# Dual_Holding_Dongle.net
KiCad netlist of a schematic drawn in Altium Designer
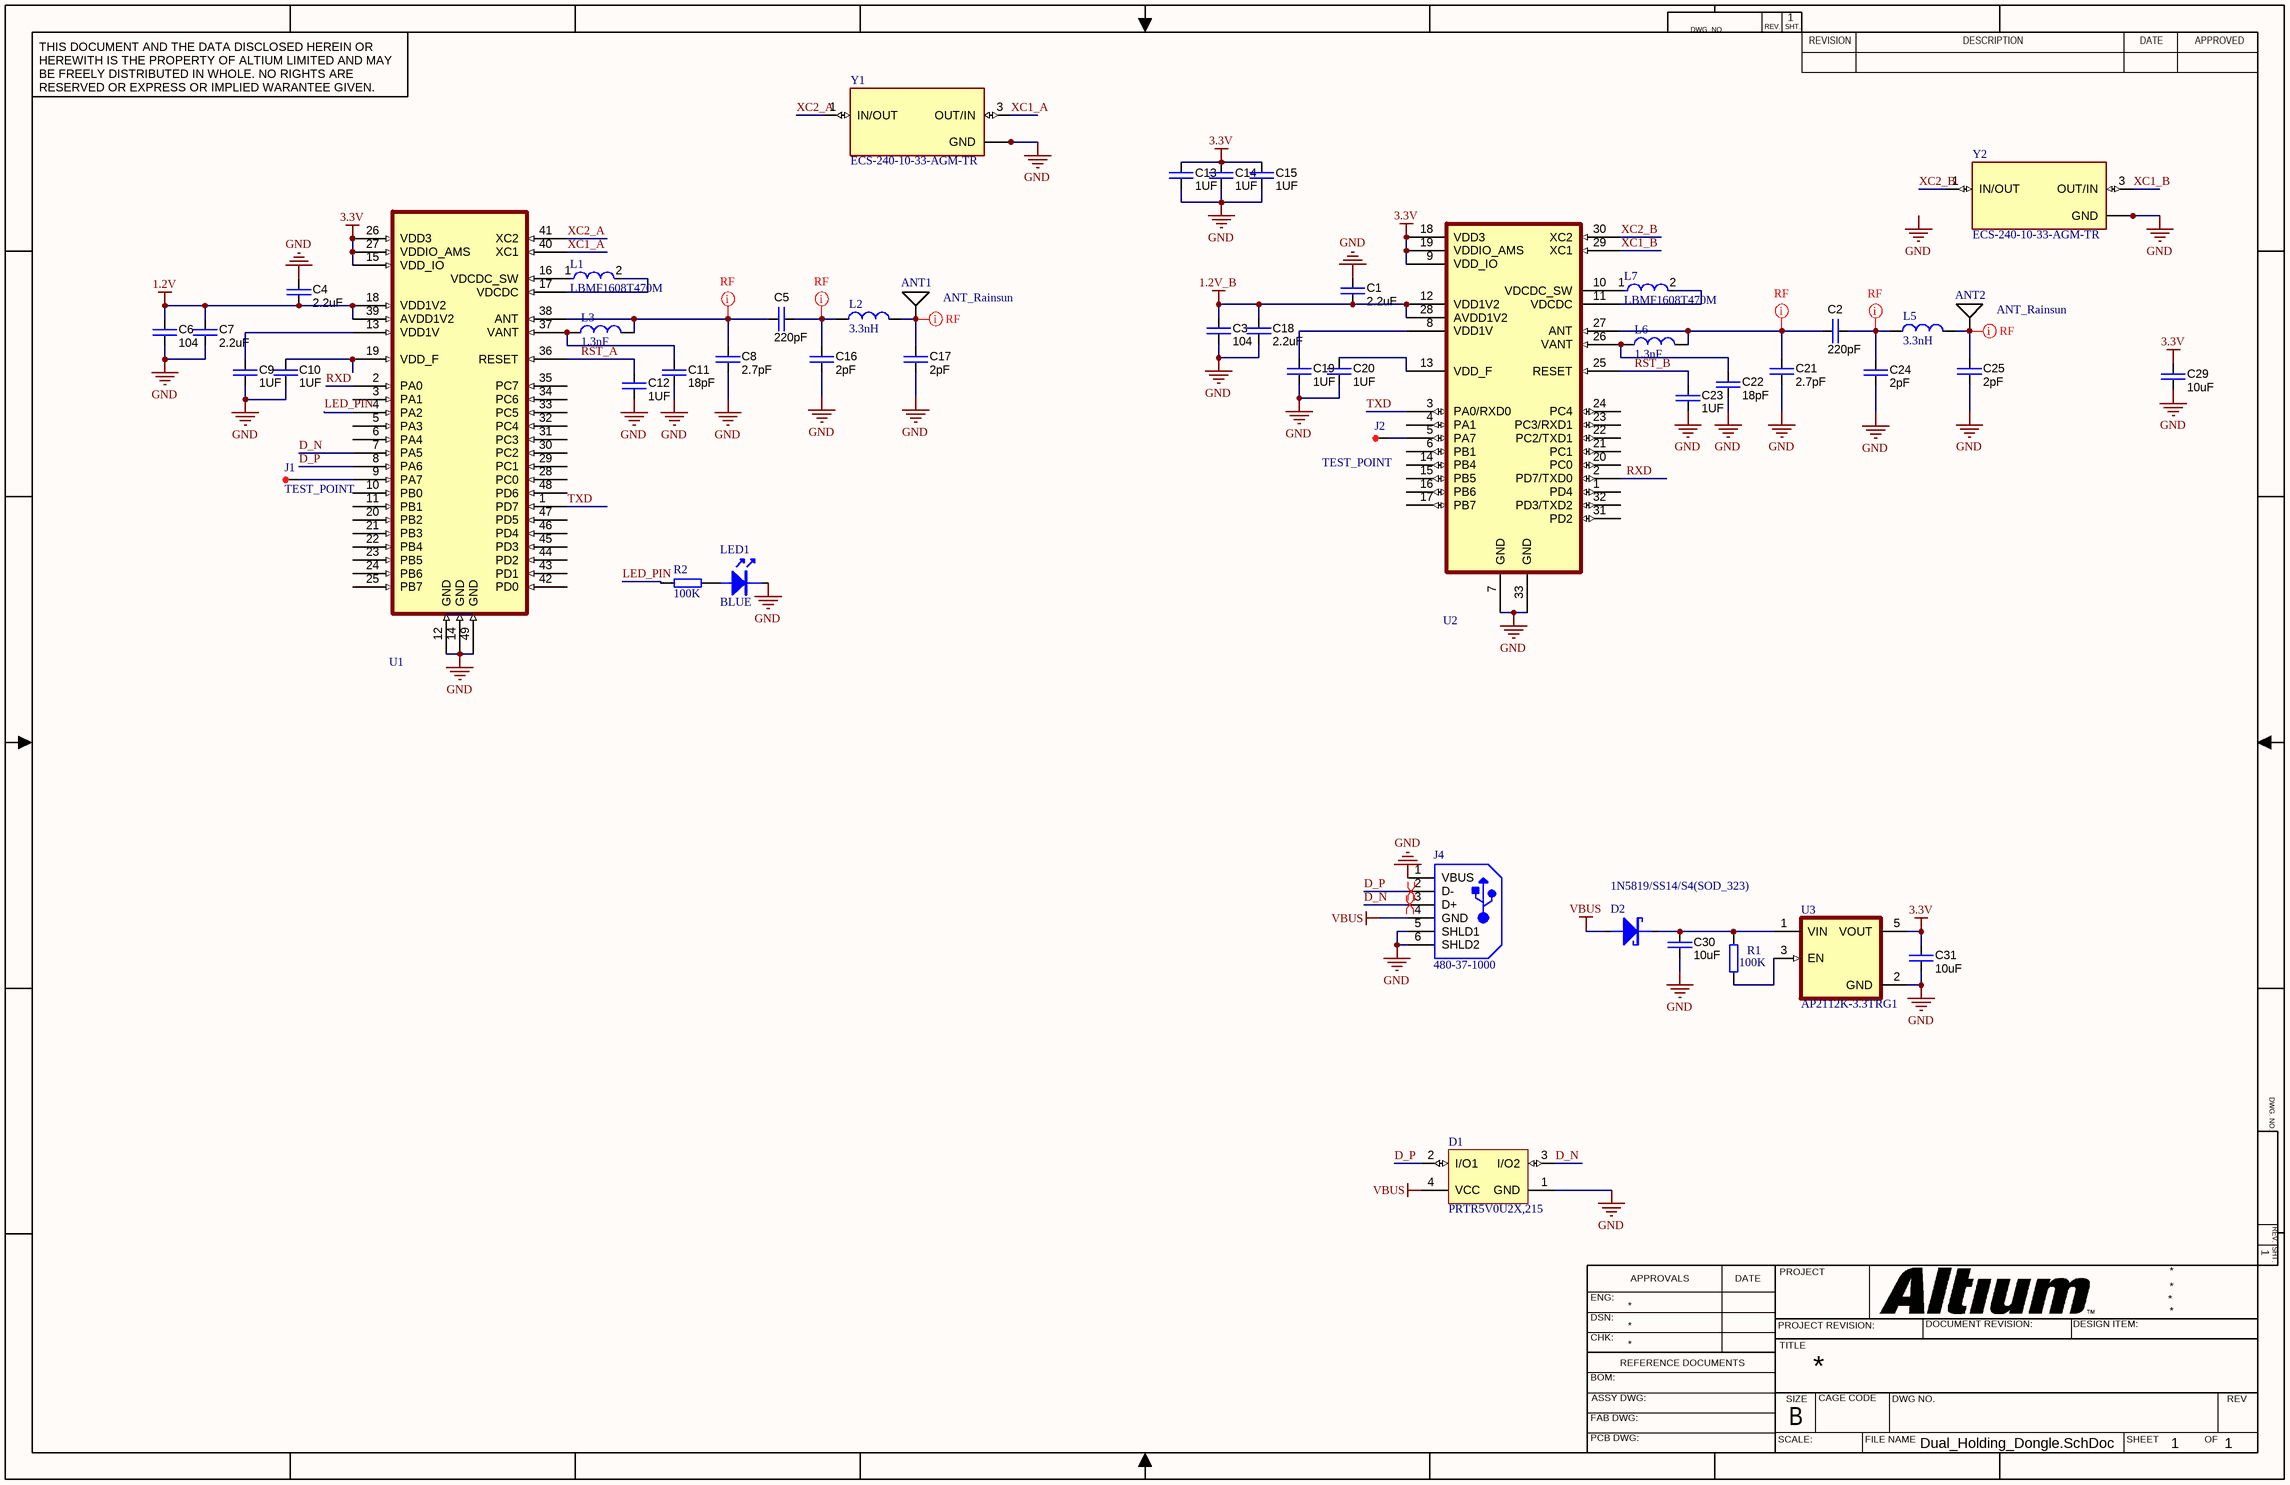
[diagram p0: Dual_Holding_Dongle.SchDoc]

(export (version "E")
  (design (tool "Eeschema 10.0.6"))
  (components
    (comp (ref "ANT1")
      (value "ANT_Rainsun")
      (footprint "ANT2-SMD-9.5X2.1X1.0MM")
      (description "318010004")
      (fields (field (name "MF") "RainSun") (field (name "MP") "AN9520"))
      (libsource (lib "WIle_dev_kit") (part "ANT_Rainsun"))
    )
    (comp (ref "ANT2")
      (value "ANT_Rainsun")
      (footprint "ANT2-SMD-9.5X2.1X1.0MM")
      (description "318010004")
      (fields (field (name "MF") "RainSun") (field (name "MP") "AN9520"))
      (libsource (lib "WIle_dev_kit") (part "ANT_Rainsun"))
    )
    (comp (ref "C1")
      (value "2.2uF")
      (footprint "CAP0402")
      (description "Capacitor SMD Cer 470nF 10% 16V X7R 0603")
      (fields (field (name "TOLERANCE") "±10%"))
      (libsource (lib "WIle_dev_kit") (part "CAP C_0603"))
    )
    (comp (ref "C2")
      (value "220pF")
      (footprint "CAP0402")
      (description "Capacitor SMD Cer 470nF 10% 16V X7R 0603")
      (fields (field (name "TOLERANCE") "±10%"))
      (libsource (lib "WIle_dev_kit") (part "CAP C_0603"))
    )
    (comp (ref "C3")
      (value "104")
      (footprint "CAP0402")
      (description "Capacitor SMD Cer 470nF 10% 16V X7R 0603")
      (fields (field (name "TOLERANCE") "±10%"))
      (libsource (lib "WIle_dev_kit") (part "CAP C_0603"))
    )
    (comp (ref "C4")
      (value "2.2uF")
      (footprint "CAP0402")
      (description "Capacitor SMD Cer 470nF 10% 16V X7R 0603")
      (fields (field (name "TOLERANCE") "±10%"))
      (libsource (lib "WIle_dev_kit") (part "CAP C_0603"))
    )
    (comp (ref "C5")
      (value "220pF")
      (footprint "CAP0402")
      (description "Capacitor SMD Cer 470nF 10% 16V X7R 0603")
      (fields (field (name "TOLERANCE") "±10%"))
      (libsource (lib "WIle_dev_kit") (part "CAP C_0603"))
    )
    (comp (ref "C6")
      (value "104")
      (footprint "CAP0402")
      (description "Capacitor SMD Cer 470nF 10% 16V X7R 0603")
      (fields (field (name "TOLERANCE") "±10%"))
      (libsource (lib "WIle_dev_kit") (part "CAP C_0603"))
    )
    (comp (ref "C7")
      (value "2.2uF")
      (footprint "CAP0402")
      (description "Capacitor SMD Cer 470nF 10% 16V X7R 0603")
      (fields (field (name "TOLERANCE") "±10%"))
      (libsource (lib "WIle_dev_kit") (part "CAP C_0603"))
    )
    (comp (ref "C8")
      (value "2.7pF")
      (footprint "CAP0402")
      (description "Capacitor SMD Cer 470nF 10% 16V X7R 0603")
      (fields (field (name "TOLERANCE") "±10%"))
      (libsource (lib "WIle_dev_kit") (part "CAP C_0603"))
    )
    (comp (ref "C9")
      (value "1UF")
      (footprint "CAP0402")
      (description "Capacitor SMD Cer 470nF 10% 16V X7R 0603")
      (fields (field (name "TOLERANCE") "±10%"))
      (libsource (lib "WIle_dev_kit") (part "CAP C_0603"))
    )
    (comp (ref "C10")
      (value "1UF")
      (footprint "CAP0402")
      (description "Capacitor SMD Cer 470nF 10% 16V X7R 0603")
      (fields (field (name "TOLERANCE") "±10%"))
      (libsource (lib "WIle_dev_kit") (part "CAP C_0603"))
    )
    (comp (ref "C11")
      (value "18pF")
      (footprint "CAP0402")
      (description "Capacitor SMD Cer 470nF 10% 16V X7R 0603")
      (fields (field (name "TOLERANCE") "±10%"))
      (libsource (lib "WIle_dev_kit") (part "CAP C_0603"))
    )
    (comp (ref "C12")
      (value "1UF")
      (footprint "CAP0402")
      (description "Capacitor SMD Cer 470nF 10% 16V X7R 0603")
      (fields (field (name "TOLERANCE") "±10%"))
      (libsource (lib "WIle_dev_kit") (part "CAP C_0603"))
    )
    (comp (ref "C13")
      (value "1UF")
      (footprint "CAPC1608X90N")
      (description "Capacitor SMD Cer 470nF 10% 16V X7R 0603")
      (fields (field (name "TOLERANCE") "±10%"))
      (libsource (lib "WIle_dev_kit") (part "CAP C_0603"))
    )
    (comp (ref "C14")
      (value "1UF")
      (footprint "CAPC1608X90N")
      (description "Capacitor SMD Cer 470nF 10% 16V X7R 0603")
      (fields (field (name "TOLERANCE") "±10%"))
      (libsource (lib "WIle_dev_kit") (part "CAP C_0603"))
    )
    (comp (ref "C15")
      (value "1UF")
      (footprint "CAPC1608X90N")
      (description "Capacitor SMD Cer 470nF 10% 16V X7R 0603")
      (fields (field (name "TOLERANCE") "±10%"))
      (libsource (lib "WIle_dev_kit") (part "CAP C_0603"))
    )
    (comp (ref "C16")
      (value "2pF")
      (footprint "CAP0402")
      (description "Capacitor SMD Cer 470nF 10% 16V X7R 0603")
      (fields (field (name "TOLERANCE") "±10%"))
      (libsource (lib "WIle_dev_kit") (part "CAP C_0603"))
    )
    (comp (ref "C17")
      (value "2pF")
      (footprint "CAP0402")
      (description "Capacitor SMD Cer 470nF 10% 16V X7R 0603")
      (fields (field (name "TOLERANCE") "±10%"))
      (libsource (lib "WIle_dev_kit") (part "CAP C_0603"))
    )
    (comp (ref "C18")
      (value "2.2uF")
      (footprint "CAP0402")
      (description "Capacitor SMD Cer 470nF 10% 16V X7R 0603")
      (fields (field (name "TOLERANCE") "±10%"))
      (libsource (lib "WIle_dev_kit") (part "CAP C_0603"))
    )
    (comp (ref "C19")
      (value "1UF")
      (footprint "CAP0402")
      (description "Capacitor SMD Cer 470nF 10% 16V X7R 0603")
      (fields (field (name "TOLERANCE") "±10%"))
      (libsource (lib "WIle_dev_kit") (part "CAP C_0603"))
    )
    (comp (ref "C20")
      (value "1UF")
      (footprint "CAP0402")
      (description "Capacitor SMD Cer 470nF 10% 16V X7R 0603")
      (fields (field (name "TOLERANCE") "±10%"))
      (libsource (lib "WIle_dev_kit") (part "CAP C_0603"))
    )
    (comp (ref "C21")
      (value "2.7pF")
      (footprint "CAP0402")
      (description "Capacitor SMD Cer 470nF 10% 16V X7R 0603")
      (fields (field (name "TOLERANCE") "±10%"))
      (libsource (lib "WIle_dev_kit") (part "CAP C_0603"))
    )
    (comp (ref "C22")
      (value "18pF")
      (footprint "CAP0402")
      (description "Capacitor SMD Cer 470nF 10% 16V X7R 0603")
      (fields (field (name "TOLERANCE") "±10%"))
      (libsource (lib "WIle_dev_kit") (part "CAP C_0603"))
    )
    (comp (ref "C23")
      (value "1UF")
      (footprint "CAP0402")
      (description "Capacitor SMD Cer 470nF 10% 16V X7R 0603")
      (fields (field (name "TOLERANCE") "±10%"))
      (libsource (lib "WIle_dev_kit") (part "CAP C_0603"))
    )
    (comp (ref "C24")
      (value "2pF")
      (footprint "CAP0402")
      (description "Capacitor SMD Cer 470nF 10% 16V X7R 0603")
      (fields (field (name "TOLERANCE") "±10%"))
      (libsource (lib "WIle_dev_kit") (part "CAP C_0603"))
    )
    (comp (ref "C25")
      (value "2pF")
      (footprint "CAP0402")
      (description "Capacitor SMD Cer 470nF 10% 16V X7R 0603")
      (fields (field (name "TOLERANCE") "±10%"))
      (libsource (lib "WIle_dev_kit") (part "CAP C_0603"))
    )
    (comp (ref "C29")
      (value "10uF")
      (footprint "CAPC1608X90N")
      (description "Capacitor SMD Cer 470nF 10% 16V X7R 0603")
      (fields (field (name "TOLERANCE") "±10%"))
      (libsource (lib "WIle_dev_kit") (part "CAP C_0603"))
    )
    (comp (ref "C30")
      (value "10uF")
      (footprint "CAPC1608X90N")
      (description "Capacitor SMD Cer 470nF 10% 16V X7R 0603")
      (fields (field (name "TOLERANCE") "±10%"))
      (libsource (lib "WIle_dev_kit") (part "CAP C_0603"))
    )
    (comp (ref "C31")
      (value "10uF")
      (footprint "CAPC1608X90N")
      (description "Capacitor SMD Cer 470nF 10% 16V X7R 0603")
      (fields (field (name "TOLERANCE") "±10%"))
      (libsource (lib "WIle_dev_kit") (part "CAP C_0603"))
    )
    (comp (ref "D1")
      (value "PRTR5V0U2X,215")
      (footprint "NXP-SOT143B-4_V")
      (fields (field (name "MANUFACTURER") "NXP Semiconductors"))
      (libsource (lib "Altium Content Vault") (part "NXP-PRTR5V0U2X,215-4"))
    )
    (comp (ref "D2")
      (value "1N5819/SS14/S4(SOD_323)")
      (footprint "SMT_DIODE_SOD_323")
      (description "Surface mount schottky diode SOD-323(0805) Package")
      (libsource (lib "WIle_dev_kit") (part "SMT_DIODE_SCHOTTKY_SOD_323"))
    )
    (comp (ref "J1")
      (value "TEST_POINT")
      (footprint "TEST_POINT_HOLE_SMALL")
      (libsource (lib "WIle_dev_kit") (part "TEST_POINT"))
    )
    (comp (ref "J2")
      (value "TEST_POINT")
      (footprint "TEST_POINT_HOLE_SMALL")
      (libsource (lib "WIle_dev_kit") (part "TEST_POINT"))
    )
    (comp (ref "J4")
      (value "480-37-1000")
      (footprint "MOLX-480-37-1000_V")
      (fields (field (name "TOLERANCE") "1%"))
      (libsource (lib "Altium Content Vault") (part "USB-4-2SHLD"))
    )
    (comp (ref "L1")
      (value "LBMF1608T470M")
      (footprint "FP-LBMF1608-0_8-0_2-IPC_B")
      (description "SMD Inductors 47uH ±20% 0.035A 3.25Ω 0603")
      (fields (field (name "TOLERANCE") "20%"))
      (libsource (lib "Altium Content Vault") (part "725321dda6339637d4d059423bc1c3c"))
    )
    (comp (ref "L2")
      (value "3.3nH")
      (footprint "IND0402")
      (description "Inductor")
      (libsource (lib "My Library") (part "Inductor"))
    )
    (comp (ref "L3")
      (value "1.3nF")
      (footprint "IND0402")
      (description "Inductor")
      (libsource (lib "My Library") (part "Inductor"))
    )
    (comp (ref "L5")
      (value "3.3nH")
      (footprint "IND0402")
      (description "Inductor")
      (libsource (lib "My Library") (part "Inductor"))
    )
    (comp (ref "L6")
      (value "1.3nF")
      (footprint "IND0402")
      (description "Inductor")
      (libsource (lib "My Library") (part "Inductor"))
    )
    (comp (ref "L7")
      (value "LBMF1608T470M")
      (footprint "FP-LBMF1608-0_8-0_2-IPC_B")
      (description "SMD Inductors 47uH ±20% 0.035A 3.25Ω 0603")
      (fields (field (name "TOLERANCE") "20%"))
      (libsource (lib "Altium Content Vault") (part "725321dda6339637d4d059423bc1c3c"))
    )
    (comp (ref "LED1")
      (value "BLUE")
      (footprint "SMT_LED_0603")
      (description "SMT LED")
      (libsource (lib "WIle_dev_kit") (part "SMT_LED_0603"))
    )
    (comp (ref "R1")
      (value "100K")
      (footprint "RES0402")
      (description "RES SM 0603 10K")
      (fields (field (name "Comment") "Resistor"))
      (libsource (lib "WIle_dev_kit") (part "RES-SM-0603-10K"))
    )
    (comp (ref "R2")
      (value "100K")
      (footprint "RES0402")
      (description "RES SM 0603 10K")
      (fields (field (name "Comment") "Resistor"))
      (libsource (lib "WIle_dev_kit") (part "RES-SM-0603-10K"))
    )
    (comp (ref "U1")
      (value "Telink TLSR8251F512ET48")
      (footprint "QFN50P700X700X80_HS-49N")
      (libsource (lib "WIle_dev_kit") (part "Telink TLSR8251F512ET48"))
    )
    (comp (ref "U2")
      (value "Telink TLSR8251F512ET32")
      (footprint "QFN50P500X500X80_HS-33N2")
      (libsource (lib "WIle_dev_kit") (part "Telink TLSR8251F512ET32"))
    )
    (comp (ref "U3")
      (value "AP2112K-3.3TRG1")
      (footprint "SOT23-5")
      (description "Linear Voltage Regulator IC 1 Output 600mA SOT-25")
      (fields
        (field (name "DIGI-KEY_PART_NUMBER") "AP2112K-3.3TRG1DICT-ND")
        (field (name "MF") "Diodes Inc.")
      )
      (libsource (lib "WIle_dev_kit") (part "AP2112K-3.3TRG1"))
    )
    (comp (ref "Y1")
      (value "ECS-240-10-33-AGM-TR")
      (footprint "XTAL_ECS-240-10-33-AGM-TR")
      (libsource (lib "ECS-240-10-33-AGM-TR") (part "ECS-240-10-33-AGM-TR"))
    )
    (comp (ref "Y2")
      (value "ECS-240-10-33-AGM-TR")
      (footprint "XTAL_ECS-240-10-33-AGM-TR")
      (libsource (lib "ECS-240-10-33-AGM-TR") (part "ECS-240-10-33-AGM-TR"))
    )
  )
  (nets
    (net (code "1") (name "/D_N") (class "Default")
      (node (ref "D1") (pin "3") (pinfunction "I/O2_3") (pintype "bidirectional"))
      (node (ref "J4") (pin "3") (pinfunction "D+_3") (pintype "passive"))
      (node (ref "U1") (pin "7") (pinfunction "PA5_7") (pintype "input"))
    )
    (net (code "2") (name "/D_P") (class "Default")
      (node (ref "D1") (pin "2") (pinfunction "I/O1_2") (pintype "bidirectional"))
      (node (ref "J4") (pin "2") (pinfunction "D-_2") (pintype "passive"))
      (node (ref "U1") (pin "8") (pinfunction "PA6_8") (pintype "input"))
    )
    (net (code "3") (name "/LED_PIN") (class "Default")
      (node (ref "R2") (pin "1") (pinfunction "1_1") (pintype "passive"))
      (node (ref "U1") (pin "4") (pinfunction "PA2_4") (pintype "input"))
    )
    (net (code "4") (name "/RST_A") (class "Default")
      (node (ref "C12") (pin "1") (pintype "passive"))
      (node (ref "U1") (pin "36") (pinfunction "RESET_36") (pintype "input"))
    )
    (net (code "5") (name "/RST_B") (class "Default")
      (node (ref "C23") (pin "1") (pintype "passive"))
      (node (ref "U2") (pin "25") (pinfunction "RESET_25") (pintype "input"))
    )
    (net (code "6") (name "/RXD") (class "Default")
      (node (ref "U1") (pin "2") (pinfunction "PA0_2") (pintype "input"))
      (node (ref "U2") (pin "2") (pinfunction "PD7/TXD0_2") (pintype "bidirectional"))
    )
    (net (code "7") (name "/TXD") (class "Default")
      (node (ref "U1") (pin "1") (pinfunction "PD7_1") (pintype "input"))
      (node (ref "U2") (pin "3") (pinfunction "PA0/RXD0_3") (pintype "bidirectional"))
    )
    (net (code "8") (name "/XC1_A") (class "Default")
      (node (ref "U1") (pin "40") (pinfunction "XC1_40") (pintype "input"))
      (node (ref "Y1") (pin "3") (pinfunction "OUT/IN_3") (pintype "bidirectional"))
    )
    (net (code "9") (name "/XC1_B") (class "Default")
      (node (ref "U2") (pin "29") (pinfunction "XC1_29") (pintype "input"))
      (node (ref "Y2") (pin "3") (pinfunction "OUT/IN_3") (pintype "bidirectional"))
    )
    (net (code "10") (name "/XC2_A") (class "Default")
      (node (ref "U1") (pin "41") (pinfunction "XC2_41") (pintype "input"))
      (node (ref "Y1") (pin "1") (pinfunction "IN/OUT_1") (pintype "bidirectional"))
    )
    (net (code "11") (name "/XC2_B") (class "Default")
      (node (ref "U2") (pin "30") (pinfunction "XC2_30") (pintype "input"))
      (node (ref "Y2") (pin "1") (pinfunction "IN/OUT_1") (pintype "bidirectional"))
    )
    (net (code "12") (name "1.2V") (class "Default")
      (node (ref "C4") (pin "1") (pintype "passive"))
      (node (ref "C6") (pin "1") (pintype "passive"))
      (node (ref "C7") (pin "1") (pintype "passive"))
      (node (ref "U1") (pin "18") (pinfunction "VDD1V2_18") (pintype "input"))
      (node (ref "U1") (pin "39") (pinfunction "AVDD1V2_39") (pintype "input"))
    )
    (net (code "13") (name "1.2V_B") (class "Default")
      (node (ref "C1") (pin "1") (pintype "passive"))
      (node (ref "C18") (pin "1") (pintype "passive"))
      (node (ref "C3") (pin "1") (pintype "passive"))
      (node (ref "U2") (pin "12") (pinfunction "VDD1V2_12") (pintype "power_in"))
      (node (ref "U2") (pin "28") (pinfunction "AVDD1V2_28") (pintype "power_in"))
    )
    (net (code "14") (name "3.3V") (class "Default")
      (node (ref "C13") (pin "1") (pintype "passive"))
      (node (ref "C14") (pin "1") (pintype "passive"))
      (node (ref "C15") (pin "1") (pintype "passive"))
      (node (ref "C29") (pin "1") (pintype "passive"))
      (node (ref "C31") (pin "1") (pintype "passive"))
      (node (ref "U1") (pin "15") (pinfunction "VDD_IO_15") (pintype "input"))
      (node (ref "U1") (pin "26") (pinfunction "VDD3_26") (pintype "input"))
      (node (ref "U1") (pin "27") (pinfunction "VDDIO_AMS_27") (pintype "input"))
      (node (ref "U2") (pin "18") (pinfunction "VDD3_18") (pintype "power_in"))
      (node (ref "U2") (pin "19") (pinfunction "VDDIO_AMS_19") (pintype "power_in"))
      (node (ref "U2") (pin "9") (pinfunction "VDD_IO_9") (pintype "power_in"))
      (node (ref "U3") (pin "5") (pinfunction "VOUT_5") (pintype "power_in"))
    )
    (net (code "15") (name "GND") (class "Default")
      (node (ref "C1") (pin "2") (pintype "passive"))
      (node (ref "C10") (pin "2") (pintype "passive"))
      (node (ref "C11") (pin "1") (pintype "passive"))
      (node (ref "C12") (pin "2") (pintype "passive"))
      (node (ref "C13") (pin "2") (pintype "passive"))
      (node (ref "C14") (pin "2") (pintype "passive"))
      (node (ref "C15") (pin "2") (pintype "passive"))
      (node (ref "C16") (pin "2") (pintype "passive"))
      (node (ref "C17") (pin "2") (pintype "passive"))
      (node (ref "C18") (pin "2") (pintype "passive"))
      (node (ref "C19") (pin "2") (pintype "passive"))
      (node (ref "C20") (pin "2") (pintype "passive"))
      (node (ref "C21") (pin "2") (pintype "passive"))
      (node (ref "C22") (pin "1") (pintype "passive"))
      (node (ref "C23") (pin "2") (pintype "passive"))
      (node (ref "C24") (pin "2") (pintype "passive"))
      (node (ref "C25") (pin "2") (pintype "passive"))
      (node (ref "C29") (pin "2") (pintype "passive"))
      (node (ref "C3") (pin "2") (pintype "passive"))
      (node (ref "C30") (pin "2") (pintype "passive"))
      (node (ref "C31") (pin "2") (pintype "passive"))
      (node (ref "C4") (pin "2") (pintype "passive"))
      (node (ref "C6") (pin "2") (pintype "passive"))
      (node (ref "C7") (pin "2") (pintype "passive"))
      (node (ref "C8") (pin "2") (pintype "passive"))
      (node (ref "C9") (pin "2") (pintype "passive"))
      (node (ref "D1") (pin "1") (pinfunction "GND_1") (pintype "power_in"))
      (node (ref "J4") (pin "1") (pinfunction "VBUS_1") (pintype "passive"))
      (node (ref "J4") (pin "5") (pinfunction "SHLD1_5") (pintype "passive"))
      (node (ref "J4") (pin "6") (pinfunction "SHLD2_6") (pintype "passive"))
      (node (ref "LED1") (pin "2") (pinfunction "K_2") (pintype "passive"))
      (node (ref "U1") (pin "12") (pinfunction "GND_12") (pintype "input"))
      (node (ref "U1") (pin "14") (pinfunction "GND_14") (pintype "input"))
      (node (ref "U1") (pin "49") (pinfunction "GND_49") (pintype "input"))
      (node (ref "U2") (pin "33") (pinfunction "GND_33") (pintype "power_in"))
      (node (ref "U2") (pin "7") (pinfunction "GND_7") (pintype "power_in"))
      (node (ref "U3") (pin "2") (pinfunction "GND_2") (pintype "power_in"))
      (node (ref "Y1") (pin "2") (pinfunction "GND_2") (pintype "power_in"))
      (node (ref "Y1") (pin "4") (pinfunction "GND_4") (pintype "power_in"))
      (node (ref "Y2") (pin "2") (pinfunction "GND_2") (pintype "power_in"))
      (node (ref "Y2") (pin "4") (pinfunction "GND_4") (pintype "power_in"))
    )
    (net (code "16") (name "Net-(ANT1-Pad1)") (class "Default")
      (node (ref "ANT1") (pin "1") (pinfunction "1_1") (pintype "passive"))
      (node (ref "C17") (pin "1") (pintype "passive"))
      (node (ref "L2") (pin "2") (pinfunction "2_2") (pintype "passive"))
    )
    (net (code "17") (name "Net-(ANT2-Pad1)") (class "Default")
      (node (ref "ANT2") (pin "1") (pinfunction "1_1") (pintype "passive"))
      (node (ref "C25") (pin "1") (pintype "passive"))
      (node (ref "L5") (pin "2") (pinfunction "2_2") (pintype "passive"))
    )
    (net (code "18") (name "Net-(C2-Pad2)") (class "Default")
      (node (ref "C2") (pin "2") (pintype "passive"))
      (node (ref "C24") (pin "1") (pintype "passive"))
      (node (ref "L5") (pin "1") (pinfunction "1_1") (pintype "passive"))
    )
    (net (code "19") (name "Net-(C16-Pad1)") (class "Default")
      (node (ref "C16") (pin "1") (pintype "passive"))
      (node (ref "C5") (pin "2") (pintype "passive"))
      (node (ref "L2") (pin "1") (pinfunction "1_1") (pintype "passive"))
    )
    (net (code "20") (name "Net-(D2-K)") (class "Default")
      (node (ref "C30") (pin "1") (pintype "passive"))
      (node (ref "D2") (pin "2") (pinfunction "K_2") (pintype "passive"))
      (node (ref "R1") (pin "1") (pinfunction "1_1") (pintype "passive"))
      (node (ref "U3") (pin "1") (pinfunction "VIN_1") (pintype "power_in"))
    )
    (net (code "21") (name "Net-(LED1-A)") (class "Default")
      (node (ref "LED1") (pin "1") (pinfunction "A_1") (pintype "passive"))
      (node (ref "R2") (pin "2") (pinfunction "2_2") (pintype "passive"))
    )
    (net (code "22") (name "Net-(U1-ANT)") (class "Default")
      (node (ref "C5") (pin "1") (pintype "passive"))
      (node (ref "C8") (pin "1") (pintype "passive"))
      (node (ref "L3") (pin "2") (pinfunction "2_2") (pintype "passive"))
      (node (ref "U1") (pin "38") (pinfunction "ANT_38") (pintype "input"))
    )
    (net (code "23") (name "Net-(U1-PA7)") (class "Default")
      (node (ref "J1") (pin "1") (pinfunction "1_1") (pintype "passive"))
      (node (ref "U1") (pin "9") (pinfunction "PA7_9") (pintype "input"))
    )
    (net (code "24") (name "Net-(U1-VANT)") (class "Default")
      (node (ref "C11") (pin "2") (pintype "passive"))
      (node (ref "L3") (pin "1") (pinfunction "1_1") (pintype "passive"))
      (node (ref "U1") (pin "37") (pinfunction "VANT_37") (pintype "input"))
    )
    (net (code "25") (name "Net-(U1-VDCDC)") (class "Default")
      (node (ref "L1") (pin "2") (pinfunction "2_2") (pintype "passive"))
      (node (ref "U1") (pin "17") (pinfunction "VDCDC_17") (pintype "input"))
    )
    (net (code "26") (name "Net-(U1-VDCDC_SW)") (class "Default")
      (node (ref "L1") (pin "1") (pinfunction "1_1") (pintype "passive"))
      (node (ref "U1") (pin "16") (pinfunction "VDCDC_SW_16") (pintype "input"))
    )
    (net (code "27") (name "Net-(U1-VDD1V)") (class "Default")
      (node (ref "C9") (pin "1") (pintype "passive"))
      (node (ref "U1") (pin "13") (pinfunction "VDD1V_13") (pintype "input"))
    )
    (net (code "28") (name "Net-(U1-VDD_F)") (class "Default")
      (node (ref "C10") (pin "1") (pintype "passive"))
      (node (ref "U1") (pin "19") (pinfunction "VDD_F_19") (pintype "input"))
    )
    (net (code "29") (name "Net-(U2-ANT)") (class "Default")
      (node (ref "C2") (pin "1") (pintype "passive"))
      (node (ref "C21") (pin "1") (pintype "passive"))
      (node (ref "L6") (pin "2") (pinfunction "2_2") (pintype "passive"))
      (node (ref "U2") (pin "27") (pinfunction "ANT_27") (pintype "input"))
    )
    (net (code "30") (name "Net-(U2-PA7)") (class "Default")
      (node (ref "J2") (pin "1") (pinfunction "1_1") (pintype "passive"))
      (node (ref "U2") (pin "5") (pinfunction "PA7_5") (pintype "bidirectional"))
    )
    (net (code "31") (name "Net-(U2-VANT)") (class "Default")
      (node (ref "C22") (pin "2") (pintype "passive"))
      (node (ref "L6") (pin "1") (pinfunction "1_1") (pintype "passive"))
      (node (ref "U2") (pin "26") (pinfunction "VANT_26") (pintype "input"))
    )
    (net (code "32") (name "Net-(U2-VDCDC)") (class "Default")
      (node (ref "L7") (pin "2") (pinfunction "2_2") (pintype "passive"))
      (node (ref "U2") (pin "11") (pinfunction "VDCDC_11") (pintype "power_in"))
    )
    (net (code "33") (name "Net-(U2-VDCDC_SW)") (class "Default")
      (node (ref "L7") (pin "1") (pinfunction "1_1") (pintype "passive"))
      (node (ref "U2") (pin "10") (pinfunction "VDCDC_SW_10") (pintype "power_in"))
    )
    (net (code "34") (name "Net-(U2-VDD1V)") (class "Default")
      (node (ref "C19") (pin "1") (pintype "passive"))
      (node (ref "U2") (pin "8") (pinfunction "VDD1V_8") (pintype "power_in"))
    )
    (net (code "35") (name "Net-(U2-VDD_F)") (class "Default")
      (node (ref "C20") (pin "1") (pintype "passive"))
      (node (ref "U2") (pin "13") (pinfunction "VDD_F_13") (pintype "power_in"))
    )
    (net (code "36") (name "Net-(U3-EN)") (class "Default")
      (node (ref "R1") (pin "2") (pinfunction "2_2") (pintype "passive"))
      (node (ref "U3") (pin "3") (pinfunction "EN_3") (pintype "input"))
    )
    (net (code "37") (name "VBUS") (class "Default")
      (node (ref "D1") (pin "4") (pinfunction "VCC_4") (pintype "power_in"))
      (node (ref "D2") (pin "1") (pinfunction "A_1") (pintype "passive"))
      (node (ref "J4") (pin "4") (pinfunction "GND_4") (pintype "passive"))
    )
    (net (code "38") (name "unconnected-(U1-PA1-Pad3)") (class "Default")
      (node (ref "U1") (pin "3") (pinfunction "PA1_3") (pintype "input"))
    )
    (net (code "39") (name "unconnected-(U1-PA3-Pad5)") (class "Default")
      (node (ref "U1") (pin "5") (pinfunction "PA3_5") (pintype "input"))
    )
    (net (code "40") (name "unconnected-(U1-PA4-Pad6)") (class "Default")
      (node (ref "U1") (pin "6") (pinfunction "PA4_6") (pintype "input"))
    )
    (net (code "41") (name "unconnected-(U1-PB0-Pad10)") (class "Default")
      (node (ref "U1") (pin "10") (pinfunction "PB0_10") (pintype "input"))
    )
    (net (code "42") (name "unconnected-(U1-PB1-Pad11)") (class "Default")
      (node (ref "U1") (pin "11") (pinfunction "PB1_11") (pintype "input"))
    )
    (net (code "43") (name "unconnected-(U1-PB2-Pad20)") (class "Default")
      (node (ref "U1") (pin "20") (pinfunction "PB2_20") (pintype "input"))
    )
    (net (code "44") (name "unconnected-(U1-PB3-Pad21)") (class "Default")
      (node (ref "U1") (pin "21") (pinfunction "PB3_21") (pintype "input"))
    )
    (net (code "45") (name "unconnected-(U1-PB4-Pad22)") (class "Default")
      (node (ref "U1") (pin "22") (pinfunction "PB4_22") (pintype "input"))
    )
    (net (code "46") (name "unconnected-(U1-PB5-Pad23)") (class "Default")
      (node (ref "U1") (pin "23") (pinfunction "PB5_23") (pintype "input"))
    )
    (net (code "47") (name "unconnected-(U1-PB6-Pad24)") (class "Default")
      (node (ref "U1") (pin "24") (pinfunction "PB6_24") (pintype "input"))
    )
    (net (code "48") (name "unconnected-(U1-PB7-Pad25)") (class "Default")
      (node (ref "U1") (pin "25") (pinfunction "PB7_25") (pintype "input"))
    )
    (net (code "49") (name "unconnected-(U1-PC0-Pad28)") (class "Default")
      (node (ref "U1") (pin "28") (pinfunction "PC0_28") (pintype "input"))
    )
    (net (code "50") (name "unconnected-(U1-PC1-Pad29)") (class "Default")
      (node (ref "U1") (pin "29") (pinfunction "PC1_29") (pintype "input"))
    )
    (net (code "51") (name "unconnected-(U1-PC2-Pad30)") (class "Default")
      (node (ref "U1") (pin "30") (pinfunction "PC2_30") (pintype "input"))
    )
    (net (code "52") (name "unconnected-(U1-PC3-Pad31)") (class "Default")
      (node (ref "U1") (pin "31") (pinfunction "PC3_31") (pintype "input"))
    )
    (net (code "53") (name "unconnected-(U1-PC4-Pad32)") (class "Default")
      (node (ref "U1") (pin "32") (pinfunction "PC4_32") (pintype "input"))
    )
    (net (code "54") (name "unconnected-(U1-PC5-Pad33)") (class "Default")
      (node (ref "U1") (pin "33") (pinfunction "PC5_33") (pintype "input"))
    )
    (net (code "55") (name "unconnected-(U1-PC6-Pad34)") (class "Default")
      (node (ref "U1") (pin "34") (pinfunction "PC6_34") (pintype "input"))
    )
    (net (code "56") (name "unconnected-(U1-PC7-Pad35)") (class "Default")
      (node (ref "U1") (pin "35") (pinfunction "PC7_35") (pintype "input"))
    )
    (net (code "57") (name "unconnected-(U1-PD0-Pad42)") (class "Default")
      (node (ref "U1") (pin "42") (pinfunction "PD0_42") (pintype "input"))
    )
    (net (code "58") (name "unconnected-(U1-PD1-Pad43)") (class "Default")
      (node (ref "U1") (pin "43") (pinfunction "PD1_43") (pintype "input"))
    )
    (net (code "59") (name "unconnected-(U1-PD2-Pad44)") (class "Default")
      (node (ref "U1") (pin "44") (pinfunction "PD2_44") (pintype "input"))
    )
    (net (code "60") (name "unconnected-(U1-PD3-Pad45)") (class "Default")
      (node (ref "U1") (pin "45") (pinfunction "PD3_45") (pintype "input"))
    )
    (net (code "61") (name "unconnected-(U1-PD4-Pad46)") (class "Default")
      (node (ref "U1") (pin "46") (pinfunction "PD4_46") (pintype "input"))
    )
    (net (code "62") (name "unconnected-(U1-PD5-Pad47)") (class "Default")
      (node (ref "U1") (pin "47") (pinfunction "PD5_47") (pintype "input"))
    )
    (net (code "63") (name "unconnected-(U1-PD6-Pad48)") (class "Default")
      (node (ref "U1") (pin "48") (pinfunction "PD6_48") (pintype "input"))
    )
    (net (code "64") (name "unconnected-(U2-PA1-Pad4)") (class "Default")
      (node (ref "U2") (pin "4") (pinfunction "PA1_4") (pintype "bidirectional"))
    )
    (net (code "65") (name "unconnected-(U2-PB1-Pad6)") (class "Default")
      (node (ref "U2") (pin "6") (pinfunction "PB1_6") (pintype "bidirectional"))
    )
    (net (code "66") (name "unconnected-(U2-PB4-Pad14)") (class "Default")
      (node (ref "U2") (pin "14") (pinfunction "PB4_14") (pintype "bidirectional"))
    )
    (net (code "67") (name "unconnected-(U2-PB5-Pad15)") (class "Default")
      (node (ref "U2") (pin "15") (pinfunction "PB5_15") (pintype "bidirectional"))
    )
    (net (code "68") (name "unconnected-(U2-PB6-Pad16)") (class "Default")
      (node (ref "U2") (pin "16") (pinfunction "PB6_16") (pintype "bidirectional"))
    )
    (net (code "69") (name "unconnected-(U2-PB7-Pad17)") (class "Default")
      (node (ref "U2") (pin "17") (pinfunction "PB7_17") (pintype "bidirectional"))
    )
    (net (code "70") (name "unconnected-(U2-PC0-Pad20)") (class "Default")
      (node (ref "U2") (pin "20") (pinfunction "PC0_20") (pintype "bidirectional"))
    )
    (net (code "71") (name "unconnected-(U2-PC1-Pad21)") (class "Default")
      (node (ref "U2") (pin "21") (pinfunction "PC1_21") (pintype "bidirectional"))
    )
    (net (code "72") (name "unconnected-(U2-PC2{slash}TXD1-Pad22)") (class "Default")
      (node (ref "U2") (pin "22") (pinfunction "PC2/TXD1_22") (pintype "bidirectional"))
    )
    (net (code "73") (name "unconnected-(U2-PC3{slash}RXD1-Pad23)") (class "Default")
      (node (ref "U2") (pin "23") (pinfunction "PC3/RXD1_23") (pintype "bidirectional"))
    )
    (net (code "74") (name "unconnected-(U2-PC4-Pad24)") (class "Default")
      (node (ref "U2") (pin "24") (pinfunction "PC4_24") (pintype "bidirectional"))
    )
    (net (code "75") (name "unconnected-(U2-PD2-Pad31)") (class "Default")
      (node (ref "U2") (pin "31") (pinfunction "PD2_31") (pintype "bidirectional"))
    )
    (net (code "76") (name "unconnected-(U2-PD3{slash}TXD2-Pad32)") (class "Default")
      (node (ref "U2") (pin "32") (pinfunction "PD3/TXD2_32") (pintype "bidirectional"))
    )
    (net (code "77") (name "unconnected-(U2-PD4-Pad1)") (class "Default")
      (node (ref "U2") (pin "1") (pinfunction "PD4_1") (pintype "bidirectional"))
    )
  )
)
